# Organ_Pedal_Module_v0_1.net
KiCad netlist of a schematic drawn in EAGLE
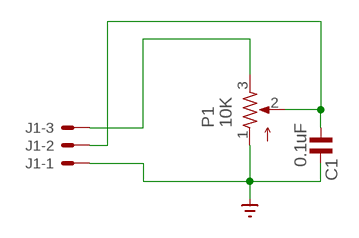
[diagram p0: schematic, sheet 1]

(export (version "E")
  (design (tool "Eeschema 10.0.6"))
  (components
    (comp (ref "C1")
      (value "0.1uF")
      (footprint "eagle-import:C0805MP")
      (libsource (lib "eagle-import") (part "C_0805MP"))
    )
    (comp (ref "J1")
      (value "22-05-7038-03")
      (footprint "eagle-import:7395-03")
      (libsource (lib "eagle-import") (part "22-?-0305-7038"))
    )
    (comp (ref "P1")
      (value "10K")
      (footprint "eagle-import:PTA6043")
      (libsource (lib "eagle-import") (part "PTA6043"))
    )
  )
  (nets
    (net (code "1") (name "GND") (class "Default")
      (node (ref "C1") (pin "2") (pinfunction "2_2") (pintype "passive"))
      (node (ref "J1") (pin "1") (pinfunction "S_1") (pintype "passive"))
      (node (ref "P1") (pin "1") (pinfunction "1_1") (pintype "passive"))
    )
    (net (code "2") (name "Net-(J1B-S)") (class "Default")
      (node (ref "C1") (pin "1") (pinfunction "1_1") (pintype "passive"))
      (node (ref "J1") (pin "2") (pinfunction "S_2") (pintype "passive"))
      (node (ref "P1") (pin "2") (pinfunction "2_2") (pintype "passive"))
    )
    (net (code "3") (name "Net-(J1C-S)") (class "Default")
      (node (ref "J1") (pin "3") (pinfunction "S_3") (pintype "passive"))
      (node (ref "P1") (pin "3") (pinfunction "3_3") (pintype "passive"))
    )
  )
)
